# BotMod.net
KiCad netlist of a schematic drawn in EAGLE
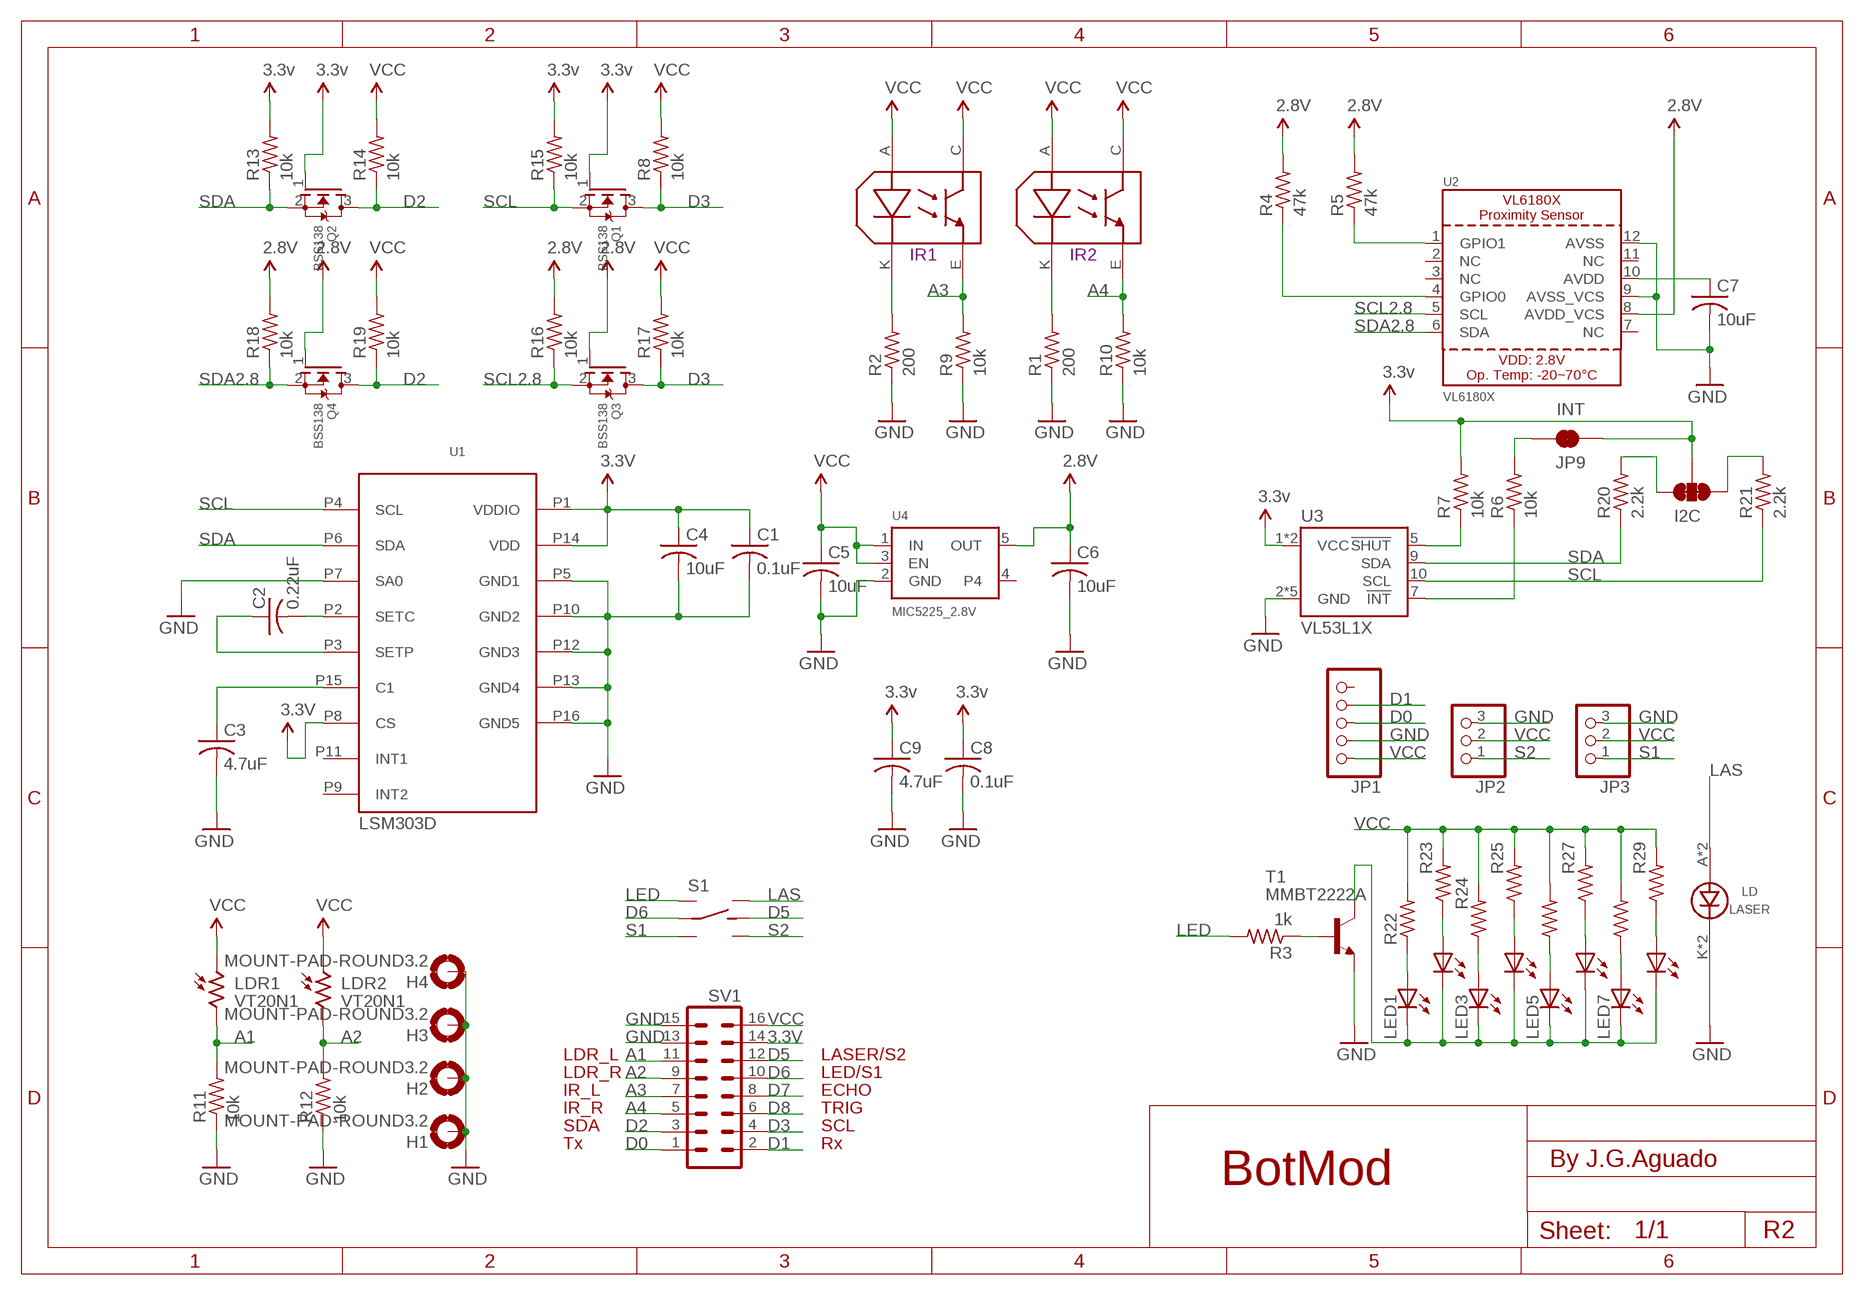
[diagram p0: schematic, sheet 1]

(export (version "E")
  (design (tool "Eeschema 10.0.6"))
  (components
    (comp (ref "C1")
      (value "0.1uF")
      (footprint "eagle-import:0402")
      (libsource (lib "eagle-import") (part "C0402"))
    )
    (comp (ref "C2")
      (value "0.22uF")
      (footprint "eagle-import:0402")
      (libsource (lib "eagle-import") (part "C0402"))
    )
    (comp (ref "C3")
      (value "4.7uF")
      (footprint "eagle-import:0402")
      (libsource (lib "eagle-import") (part "C0402"))
    )
    (comp (ref "C4")
      (value "10uF")
      (footprint "eagle-import:0402")
      (libsource (lib "eagle-import") (part "C0402"))
    )
    (comp (ref "C5")
      (value "10uF")
      (footprint "eagle-import:0402")
      (libsource (lib "eagle-import") (part "C0402"))
    )
    (comp (ref "C6")
      (value "10uF")
      (footprint "eagle-import:0402")
      (libsource (lib "eagle-import") (part "C0402"))
    )
    (comp (ref "C7")
      (value "10uF")
      (footprint "eagle-import:0402")
      (libsource (lib "eagle-import") (part "C0402"))
    )
    (comp (ref "C8")
      (value "0.1uF")
      (footprint "eagle-import:0402")
      (libsource (lib "eagle-import") (part "C0402"))
    )
    (comp (ref "C9")
      (value "4.7uF")
      (footprint "eagle-import:0402")
      (libsource (lib "eagle-import") (part "C0402"))
    )
    (comp (ref "H1")
      (value "MOUNT-PAD-ROUND3.2")
      (footprint "eagle-import:3,2-PAD")
      (libsource (lib "eagle-import") (part "MOUNT-PAD-ROUND3.2"))
    )
    (comp (ref "H2")
      (value "MOUNT-PAD-ROUND3.2")
      (footprint "eagle-import:3,2-PAD")
      (libsource (lib "eagle-import") (part "MOUNT-PAD-ROUND3.2"))
    )
    (comp (ref "H3")
      (value "MOUNT-PAD-ROUND3.2")
      (footprint "eagle-import:3,2-PAD")
      (libsource (lib "eagle-import") (part "MOUNT-PAD-ROUND3.2"))
    )
    (comp (ref "H4")
      (value "MOUNT-PAD-ROUND3.2")
      (footprint "eagle-import:3,2-PAD")
      (libsource (lib "eagle-import") (part "MOUNT-PAD-ROUND3.2"))
    )
    (comp (ref "I2C")
      (value "JUMPER-SMT_3_2-NC_TRACE_SILK")
      (footprint "eagle-import:SMT-JUMPER_3_2-NC_TRACE_SILK")
      (libsource (lib "eagle-import") (part "JUMPER-SMT_3_2-NC_TRACE_SILK"))
    )
    (comp (ref "IR1")
      (value "IR_TCRT5000")
      (footprint "eagle-import:IR_TCRT5000")
      (libsource (lib "eagle-import") (part "IR_TCRT5000"))
    )
    (comp (ref "IR2")
      (value "IR_TCRT5000")
      (footprint "eagle-import:IR_TCRT5000")
      (libsource (lib "eagle-import") (part "IR_TCRT5000"))
    )
    (comp (ref "JP1")
      (value "PINHEAD_5_FEMALE")
      (footprint "eagle-import:PINHEAD_5_FEMALE")
      (libsource (lib "eagle-import") (part "PINHEAD_5_FEMALE"))
    )
    (comp (ref "JP2")
      (value "PINHD-1X3")
      (footprint "eagle-import:1X03")
      (libsource (lib "eagle-import") (part "PINHD-1X3"))
    )
    (comp (ref "JP3")
      (value "PINHD-1X3")
      (footprint "eagle-import:1X03")
      (libsource (lib "eagle-import") (part "PINHD-1X3"))
    )
    (comp (ref "JP9")
      (value "INT")
      (footprint "eagle-import:PAD-JUMPER-2-NC_BY_TRACE_YES_SILK")
      (libsource (lib "eagle-import") (part "JUMPER-PAD-2-NC_BY_TRACE"))
    )
    (comp (ref "LD")
      (value "LASER")
      (footprint "eagle-import:KEYES_LASER")
      (libsource (lib "eagle-import") (part "KEYES_LASER"))
    )
    (comp (ref "LDR1")
      (value "VT20N1")
      (footprint "eagle-import:TO46-VT200")
      (libsource (lib "eagle-import") (part "VT20N1"))
    )
    (comp (ref "LDR2")
      (value "VT20N1")
      (footprint "eagle-import:TO46-VT200")
      (libsource (lib "eagle-import") (part "VT20N1"))
    )
    (comp (ref "LED1")
      (value "LED5730")
      (footprint "eagle-import:LED5730")
      (libsource (lib "eagle-import") (part "LED5730"))
    )
    (comp (ref "LED2")
      (value "LED5730")
      (footprint "eagle-import:LED5730")
      (libsource (lib "eagle-import") (part "LED5730"))
    )
    (comp (ref "LED3")
      (value "LED5730")
      (footprint "eagle-import:LED5730")
      (libsource (lib "eagle-import") (part "LED5730"))
    )
    (comp (ref "LED4")
      (value "LED5730")
      (footprint "eagle-import:LED5730")
      (libsource (lib "eagle-import") (part "LED5730"))
    )
    (comp (ref "LED5")
      (value "LED5730")
      (footprint "eagle-import:LED5730")
      (libsource (lib "eagle-import") (part "LED5730"))
    )
    (comp (ref "LED6")
      (value "LED5730")
      (footprint "eagle-import:LED5730")
      (libsource (lib "eagle-import") (part "LED5730"))
    )
    (comp (ref "LED7")
      (value "LED5730")
      (footprint "eagle-import:LED5730")
      (libsource (lib "eagle-import") (part "LED5730"))
    )
    (comp (ref "LED8")
      (value "LED5730")
      (footprint "eagle-import:LED5730")
      (libsource (lib "eagle-import") (part "LED5730"))
    )
    (comp (ref "Q1")
      (value "BSS138")
      (footprint "eagle-import:SOT23")
      (libsource (lib "eagle-import") (part "MOSFET-NREFLOW"))
    )
    (comp (ref "Q2")
      (value "BSS138")
      (footprint "eagle-import:SOT23")
      (libsource (lib "eagle-import") (part "MOSFET-NREFLOW"))
    )
    (comp (ref "Q3")
      (value "BSS138")
      (footprint "eagle-import:SOT23")
      (libsource (lib "eagle-import") (part "MOSFET-NREFLOW"))
    )
    (comp (ref "Q4")
      (value "BSS138")
      (footprint "eagle-import:SOT23")
      (libsource (lib "eagle-import") (part "MOSFET-NREFLOW"))
    )
    (comp (ref "R1")
      (value "200")
      (footprint "eagle-import:0402")
      (libsource (lib "eagle-import") (part "R0402"))
    )
    (comp (ref "R2")
      (value "200")
      (footprint "eagle-import:0402")
      (libsource (lib "eagle-import") (part "R0402"))
    )
    (comp (ref "R3")
      (value "1k")
      (footprint "eagle-import:0402")
      (libsource (lib "eagle-import") (part "R0402"))
    )
    (comp (ref "R4")
      (value "47k")
      (footprint "eagle-import:0402")
      (libsource (lib "eagle-import") (part "R0402"))
    )
    (comp (ref "R5")
      (value "47k")
      (footprint "eagle-import:0402")
      (libsource (lib "eagle-import") (part "R0402"))
    )
    (comp (ref "R6")
      (value "10k")
      (footprint "eagle-import:0402")
      (libsource (lib "eagle-import") (part "R0402"))
    )
    (comp (ref "R7")
      (value "10k")
      (footprint "eagle-import:0402")
      (libsource (lib "eagle-import") (part "R0402"))
    )
    (comp (ref "R8")
      (value "10k")
      (footprint "eagle-import:0402")
      (libsource (lib "eagle-import") (part "R0402"))
    )
    (comp (ref "R9")
      (value "10k")
      (footprint "eagle-import:0402")
      (libsource (lib "eagle-import") (part "R0402"))
    )
    (comp (ref "R10")
      (value "10k")
      (footprint "eagle-import:0402")
      (libsource (lib "eagle-import") (part "R0402"))
    )
    (comp (ref "R11")
      (value "10k")
      (footprint "eagle-import:0402")
      (libsource (lib "eagle-import") (part "R0402"))
    )
    (comp (ref "R12")
      (value "10k")
      (footprint "eagle-import:0402")
      (libsource (lib "eagle-import") (part "R0402"))
    )
    (comp (ref "R13")
      (value "10k")
      (footprint "eagle-import:0402")
      (libsource (lib "eagle-import") (part "R0402"))
    )
    (comp (ref "R14")
      (value "10k")
      (footprint "eagle-import:0402")
      (libsource (lib "eagle-import") (part "R0402"))
    )
    (comp (ref "R15")
      (value "10k")
      (footprint "eagle-import:0402")
      (libsource (lib "eagle-import") (part "R0402"))
    )
    (comp (ref "R16")
      (value "10k")
      (footprint "eagle-import:0402")
      (libsource (lib "eagle-import") (part "R0402"))
    )
    (comp (ref "R17")
      (value "10k")
      (footprint "eagle-import:0402")
      (libsource (lib "eagle-import") (part "R0402"))
    )
    (comp (ref "R18")
      (value "10k")
      (footprint "eagle-import:0402")
      (libsource (lib "eagle-import") (part "R0402"))
    )
    (comp (ref "R19")
      (value "10k")
      (footprint "eagle-import:0402")
      (libsource (lib "eagle-import") (part "R0402"))
    )
    (comp (ref "R20")
      (value "2.2k")
      (footprint "eagle-import:0402")
      (libsource (lib "eagle-import") (part "R0402"))
    )
    (comp (ref "R21")
      (value "2.2k")
      (footprint "eagle-import:0402")
      (libsource (lib "eagle-import") (part "R0402"))
    )
    (comp (ref "R22")
      (value "R1206")
      (footprint "eagle-import:1206")
      (libsource (lib "eagle-import") (part "R1206"))
    )
    (comp (ref "R23")
      (value "R1206")
      (footprint "eagle-import:1206")
      (libsource (lib "eagle-import") (part "R1206"))
    )
    (comp (ref "R24")
      (value "R1206")
      (footprint "eagle-import:1206")
      (libsource (lib "eagle-import") (part "R1206"))
    )
    (comp (ref "R25")
      (value "R1206")
      (footprint "eagle-import:1206")
      (libsource (lib "eagle-import") (part "R1206"))
    )
    (comp (ref "R26")
      (value "R1206")
      (footprint "eagle-import:1206")
      (libsource (lib "eagle-import") (part "R1206"))
    )
    (comp (ref "R27")
      (value "R1206")
      (footprint "eagle-import:1206")
      (libsource (lib "eagle-import") (part "R1206"))
    )
    (comp (ref "R28")
      (value "R1206")
      (footprint "eagle-import:1206")
      (libsource (lib "eagle-import") (part "R1206"))
    )
    (comp (ref "R29")
      (value "R1206")
      (footprint "eagle-import:1206")
      (libsource (lib "eagle-import") (part "R1206"))
    )
    (comp (ref "S1")
      (value "DPDT_JS202011CQN")
      (footprint "eagle-import:DPDT_JS202011CQN")
      (libsource (lib "eagle-import") (part "DPDT_JS202011CQN"))
    )
    (comp (ref "SV1")
      (value "MA08-2")
      (footprint "eagle-import:MA08-2")
      (libsource (lib "eagle-import") (part "MA08-2"))
    )
    (comp (ref "T1")
      (value "MMBT2222A")
      (footprint "eagle-import:SOT23-BEC")
      (libsource (lib "eagle-import") (part "-NPN-SOT23-BECBC808"))
    )
    (comp (ref "U1")
      (value "LSM303D")
      (footprint "eagle-import:LGA3X3_16L")
      (libsource (lib "eagle-import") (part "LSM303D"))
    )
    (comp (ref "U2")
      (value "VL6180X")
      (footprint "eagle-import:VL6180")
      (libsource (lib "eagle-import") (part "VL6180X"))
    )
    (comp (ref "U3")
      (value "VL53L1X")
      (footprint "eagle-import:VL53L1X")
      (libsource (lib "eagle-import") (part "VL53L1XSMD"))
    )
    (comp (ref "U4")
      (value "MIC5225_2.8V")
      (footprint "eagle-import:SOT23-5")
      (libsource (lib "eagle-import") (part "VREG_SOT23-5"))
    )
  )
  (nets
    (net (code "1") (name "/A1") (class "Default")
      (node (ref "LDR1") (pin "2") (pinfunction "2_2") (pintype "passive"))
      (node (ref "R11") (pin "2") (pinfunction "2_2") (pintype "passive"))
      (node (ref "SV1") (pin "11") (pinfunction "11_11") (pintype "passive"))
    )
    (net (code "2") (name "/A2") (class "Default")
      (node (ref "LDR2") (pin "2") (pinfunction "2_2") (pintype "passive"))
      (node (ref "R12") (pin "2") (pinfunction "2_2") (pintype "passive"))
      (node (ref "SV1") (pin "9") (pinfunction "9_9") (pintype "passive"))
    )
    (net (code "3") (name "/A3") (class "Default")
      (node (ref "IR1") (pin "E") (pinfunction "E_E") (pintype "bidirectional"))
      (node (ref "R9") (pin "2") (pinfunction "2_2") (pintype "passive"))
      (node (ref "SV1") (pin "7") (pinfunction "7_7") (pintype "passive"))
    )
    (net (code "4") (name "/A4") (class "Default")
      (node (ref "IR2") (pin "E") (pinfunction "E_E") (pintype "bidirectional"))
      (node (ref "R10") (pin "2") (pinfunction "2_2") (pintype "passive"))
      (node (ref "SV1") (pin "5") (pinfunction "5_5") (pintype "passive"))
    )
    (net (code "5") (name "/D0") (class "Default")
      (node (ref "JP1") (pin "P$3") (pinfunction "3_P$3") (pintype "passive"))
      (node (ref "SV1") (pin "1") (pinfunction "1_1") (pintype "passive"))
    )
    (net (code "6") (name "/D1") (class "Default")
      (node (ref "JP1") (pin "P$4") (pinfunction "4_P$4") (pintype "passive"))
      (node (ref "SV1") (pin "2") (pinfunction "2_2") (pintype "passive"))
    )
    (net (code "7") (name "/D2") (class "Default")
      (node (ref "Q2") (pin "3") (pinfunction "D_3") (pintype "bidirectional"))
      (node (ref "Q4") (pin "3") (pinfunction "D_3") (pintype "bidirectional"))
      (node (ref "R14") (pin "1") (pinfunction "1_1") (pintype "passive"))
      (node (ref "R19") (pin "1") (pinfunction "1_1") (pintype "passive"))
      (node (ref "SV1") (pin "3") (pinfunction "3_3") (pintype "passive"))
    )
    (net (code "8") (name "/D3") (class "Default")
      (node (ref "Q1") (pin "3") (pinfunction "D_3") (pintype "bidirectional"))
      (node (ref "Q3") (pin "3") (pinfunction "D_3") (pintype "bidirectional"))
      (node (ref "R17") (pin "1") (pinfunction "1_1") (pintype "passive"))
      (node (ref "R8") (pin "1") (pinfunction "1_1") (pintype "passive"))
      (node (ref "SV1") (pin "4") (pinfunction "4_4") (pintype "passive"))
    )
    (net (code "9") (name "/D5") (class "Default")
      (node (ref "S1") (pin "5") (pinfunction "RC_5") (pintype "passive"))
      (node (ref "SV1") (pin "12") (pinfunction "12_12") (pintype "passive"))
    )
    (net (code "10") (name "/D6") (class "Default")
      (node (ref "S1") (pin "2") (pinfunction "LC_2") (pintype "passive"))
      (node (ref "SV1") (pin "10") (pinfunction "10_10") (pintype "passive"))
    )
    (net (code "11") (name "/D7") (class "Default")
      (node (ref "SV1") (pin "8") (pinfunction "8_8") (pintype "passive"))
    )
    (net (code "12") (name "/D8") (class "Default")
      (node (ref "SV1") (pin "6") (pinfunction "6_6") (pintype "passive"))
    )
    (net (code "13") (name "/LAS") (class "Default")
      (node (ref "LD") (pin "A") (pinfunction "A_A") (pintype "bidirectional"))
      (node (ref "LD") (pin "A1") (pinfunction "A_A1") (pintype "bidirectional"))
      (node (ref "S1") (pin "4") (pinfunction "R1_4") (pintype "passive"))
    )
    (net (code "14") (name "/LED") (class "Default")
      (node (ref "R3") (pin "2") (pinfunction "2_2") (pintype "passive"))
      (node (ref "S1") (pin "1") (pinfunction "L1_1") (pintype "passive"))
    )
    (net (code "15") (name "/S1") (class "Default")
      (node (ref "JP3") (pin "1") (pinfunction "1_1") (pintype "passive"))
      (node (ref "S1") (pin "3") (pinfunction "L2_3") (pintype "passive"))
    )
    (net (code "16") (name "/S2") (class "Default")
      (node (ref "JP2") (pin "1") (pinfunction "1_1") (pintype "passive"))
      (node (ref "S1") (pin "6") (pinfunction "R2_6") (pintype "passive"))
    )
    (net (code "17") (name "/SCL") (class "Default")
      (node (ref "Q1") (pin "2") (pinfunction "S_2") (pintype "bidirectional"))
      (node (ref "R15") (pin "1") (pinfunction "1_1") (pintype "passive"))
      (node (ref "R21") (pin "1") (pinfunction "1_1") (pintype "passive"))
      (node (ref "U1") (pin "P4") (pinfunction "SCL_P4") (pintype "bidirectional"))
      (node (ref "U3") (pin "10") (pinfunction "SCL_10") (pintype "bidirectional"))
    )
    (net (code "18") (name "/SCL2.8") (class "Default")
      (node (ref "Q3") (pin "2") (pinfunction "S_2") (pintype "bidirectional"))
      (node (ref "R16") (pin "1") (pinfunction "1_1") (pintype "passive"))
      (node (ref "U2") (pin "5") (pinfunction "SCL_5") (pintype "input"))
    )
    (net (code "19") (name "/SDA") (class "Default")
      (node (ref "Q2") (pin "2") (pinfunction "S_2") (pintype "bidirectional"))
      (node (ref "R13") (pin "1") (pinfunction "1_1") (pintype "passive"))
      (node (ref "R20") (pin "1") (pinfunction "1_1") (pintype "passive"))
      (node (ref "U1") (pin "P6") (pinfunction "SDA_P6") (pintype "bidirectional"))
      (node (ref "U3") (pin "9") (pinfunction "SDA_9") (pintype "bidirectional"))
    )
    (net (code "20") (name "/SDA2.8") (class "Default")
      (node (ref "Q4") (pin "2") (pinfunction "S_2") (pintype "bidirectional"))
      (node (ref "R18") (pin "1") (pinfunction "1_1") (pintype "passive"))
      (node (ref "U2") (pin "6") (pinfunction "SDA_6") (pintype "bidirectional"))
    )
    (net (code "21") (name "2.8V") (class "Default")
      (node (ref "C6") (pin "1") (pinfunction "1_1") (pintype "passive"))
      (node (ref "Q3") (pin "1") (pinfunction "G_1") (pintype "bidirectional"))
      (node (ref "Q4") (pin "1") (pinfunction "G_1") (pintype "bidirectional"))
      (node (ref "R16") (pin "2") (pinfunction "2_2") (pintype "passive"))
      (node (ref "R18") (pin "2") (pinfunction "2_2") (pintype "passive"))
      (node (ref "R4") (pin "2") (pinfunction "2_2") (pintype "passive"))
      (node (ref "R5") (pin "2") (pinfunction "2_2") (pintype "passive"))
      (node (ref "U2") (pin "8") (pinfunction "AVDD_VCS_8") (pintype "power_in"))
      (node (ref "U4") (pin "5") (pinfunction "OUT_5") (pintype "power_in"))
    )
    (net (code "22") (name "3.3V") (class "Default")
      (node (ref "C1") (pin "1") (pinfunction "1_1") (pintype "passive"))
      (node (ref "C4") (pin "1") (pinfunction "1_1") (pintype "passive"))
      (node (ref "C8") (pin "1") (pinfunction "1_1") (pintype "passive"))
      (node (ref "C9") (pin "1") (pinfunction "1_1") (pintype "passive"))
      (node (ref "I2C") (pin "2") (pinfunction "2_2") (pintype "passive"))
      (node (ref "JP9") (pin "1") (pinfunction "1_1") (pintype "passive"))
      (node (ref "Q1") (pin "1") (pinfunction "G_1") (pintype "bidirectional"))
      (node (ref "Q2") (pin "1") (pinfunction "G_1") (pintype "bidirectional"))
      (node (ref "R13") (pin "2") (pinfunction "2_2") (pintype "passive"))
      (node (ref "R15") (pin "2") (pinfunction "2_2") (pintype "passive"))
      (node (ref "R7") (pin "2") (pinfunction "2_2") (pintype "passive"))
      (node (ref "SV1") (pin "14") (pinfunction "14_14") (pintype "passive"))
      (node (ref "U1") (pin "P1") (pinfunction "VDDIO_P1") (pintype "bidirectional"))
      (node (ref "U1") (pin "P14") (pinfunction "VDD_P14") (pintype "bidirectional"))
      (node (ref "U1") (pin "P8") (pinfunction "CS_P8") (pintype "bidirectional"))
      (node (ref "U3") (pin "1") (pinfunction "VCC_1") (pintype "bidirectional"))
      (node (ref "U3") (pin "11") (pinfunction "VCC_11") (pintype "bidirectional"))
    )
    (net (code "23") (name "GND") (class "Default")
      (node (ref "C1") (pin "2") (pinfunction "2_2") (pintype "passive"))
      (node (ref "C3") (pin "2") (pinfunction "2_2") (pintype "passive"))
      (node (ref "C4") (pin "2") (pinfunction "2_2") (pintype "passive"))
      (node (ref "C5") (pin "2") (pinfunction "2_2") (pintype "passive"))
      (node (ref "C6") (pin "2") (pinfunction "2_2") (pintype "passive"))
      (node (ref "C7") (pin "2") (pinfunction "2_2") (pintype "passive"))
      (node (ref "C8") (pin "2") (pinfunction "2_2") (pintype "passive"))
      (node (ref "C9") (pin "2") (pinfunction "2_2") (pintype "passive"))
      (node (ref "H1") (pin "B3,2") (pinfunction "MOUNT_B3,2") (pintype "passive"))
      (node (ref "H2") (pin "B3,2") (pinfunction "MOUNT_B3,2") (pintype "passive"))
      (node (ref "H3") (pin "B3,2") (pinfunction "MOUNT_B3,2") (pintype "passive"))
      (node (ref "H4") (pin "B3,2") (pinfunction "MOUNT_B3,2") (pintype "passive"))
      (node (ref "JP1") (pin "P$2") (pinfunction "2_P$2") (pintype "passive"))
      (node (ref "JP2") (pin "3") (pinfunction "3_3") (pintype "passive"))
      (node (ref "JP3") (pin "3") (pinfunction "3_3") (pintype "passive"))
      (node (ref "LD") (pin "K") (pinfunction "K_K") (pintype "bidirectional"))
      (node (ref "LD") (pin "K1") (pinfunction "K_K1") (pintype "bidirectional"))
      (node (ref "R1") (pin "1") (pinfunction "1_1") (pintype "passive"))
      (node (ref "R10") (pin "1") (pinfunction "1_1") (pintype "passive"))
      (node (ref "R11") (pin "1") (pinfunction "1_1") (pintype "passive"))
      (node (ref "R12") (pin "1") (pinfunction "1_1") (pintype "passive"))
      (node (ref "R2") (pin "1") (pinfunction "1_1") (pintype "passive"))
      (node (ref "R9") (pin "1") (pinfunction "1_1") (pintype "passive"))
      (node (ref "SV1") (pin "13") (pinfunction "13_13") (pintype "passive"))
      (node (ref "SV1") (pin "15") (pinfunction "15_15") (pintype "passive"))
      (node (ref "T1") (pin "E") (pinfunction "E_E") (pintype "passive"))
      (node (ref "U1") (pin "P10") (pinfunction "GND2_P10") (pintype "bidirectional"))
      (node (ref "U1") (pin "P12") (pinfunction "GND3_P12") (pintype "bidirectional"))
      (node (ref "U1") (pin "P13") (pinfunction "GND4_P13") (pintype "bidirectional"))
      (node (ref "U1") (pin "P16") (pinfunction "GND5_P16") (pintype "bidirectional"))
      (node (ref "U1") (pin "P5") (pinfunction "GND1_P5") (pintype "bidirectional"))
      (node (ref "U1") (pin "P7") (pinfunction "SA0_P7") (pintype "bidirectional"))
      (node (ref "U2") (pin "12") (pinfunction "AVSS_12") (pintype "power_in"))
      (node (ref "U2") (pin "9") (pinfunction "AVSS_VCS_9") (pintype "power_in"))
      (node (ref "U3") (pin "12") (pinfunction "GND_12") (pintype "bidirectional"))
      (node (ref "U3") (pin "2") (pinfunction "GND_2") (pintype "bidirectional"))
      (node (ref "U3") (pin "3") (pinfunction "GND_3") (pintype "bidirectional"))
      (node (ref "U3") (pin "4") (pinfunction "GND_4") (pintype "bidirectional"))
      (node (ref "U3") (pin "6") (pinfunction "GND_6") (pintype "bidirectional"))
      (node (ref "U4") (pin "2") (pinfunction "GND_2") (pintype "power_in"))
    )
    (net (code "24") (name "Net-(I2C-Pad1)") (class "Default")
      (node (ref "I2C") (pin "1") (pinfunction "1_1") (pintype "passive"))
      (node (ref "R21") (pin "2") (pinfunction "2_2") (pintype "passive"))
    )
    (net (code "25") (name "Net-(I2C-Pad3)") (class "Default")
      (node (ref "I2C") (pin "3") (pinfunction "3_3") (pintype "passive"))
      (node (ref "R20") (pin "2") (pinfunction "2_2") (pintype "passive"))
    )
    (net (code "26") (name "Net-(IR1-PadK)") (class "Default")
      (node (ref "IR1") (pin "K") (pinfunction "K_K") (pintype "bidirectional"))
      (node (ref "R2") (pin "2") (pinfunction "2_2") (pintype "passive"))
    )
    (net (code "27") (name "Net-(IR2-PadK)") (class "Default")
      (node (ref "IR2") (pin "K") (pinfunction "K_K") (pintype "bidirectional"))
      (node (ref "R1") (pin "2") (pinfunction "2_2") (pintype "passive"))
    )
    (net (code "28") (name "Net-(JP9-Pad2)") (class "Default")
      (node (ref "JP9") (pin "2") (pinfunction "2_2") (pintype "passive"))
      (node (ref "R6") (pin "2") (pinfunction "2_2") (pintype "passive"))
    )
    (net (code "29") (name "Net-(LED1-A)") (class "Default")
      (node (ref "LED1") (pin "P$1") (pinfunction "A_P$1") (pintype "passive"))
      (node (ref "R22") (pin "1") (pinfunction "1_1") (pintype "passive"))
    )
    (net (code "30") (name "Net-(LED1-C)") (class "Default")
      (node (ref "LED1") (pin "P$2") (pinfunction "C_P$2") (pintype "passive"))
      (node (ref "LED2") (pin "P$2") (pinfunction "C_P$2") (pintype "passive"))
      (node (ref "LED3") (pin "P$2") (pinfunction "C_P$2") (pintype "passive"))
      (node (ref "LED4") (pin "P$2") (pinfunction "C_P$2") (pintype "passive"))
      (node (ref "LED5") (pin "P$2") (pinfunction "C_P$2") (pintype "passive"))
      (node (ref "LED6") (pin "P$2") (pinfunction "C_P$2") (pintype "passive"))
      (node (ref "LED7") (pin "P$2") (pinfunction "C_P$2") (pintype "passive"))
      (node (ref "LED8") (pin "P$2") (pinfunction "C_P$2") (pintype "passive"))
      (node (ref "T1") (pin "C") (pinfunction "C_C") (pintype "passive"))
    )
    (net (code "31") (name "Net-(LED2-A)") (class "Default")
      (node (ref "LED2") (pin "P$1") (pinfunction "A_P$1") (pintype "passive"))
      (node (ref "R23") (pin "1") (pinfunction "1_1") (pintype "passive"))
    )
    (net (code "32") (name "Net-(LED3-A)") (class "Default")
      (node (ref "LED3") (pin "P$1") (pinfunction "A_P$1") (pintype "passive"))
      (node (ref "R24") (pin "1") (pinfunction "1_1") (pintype "passive"))
    )
    (net (code "33") (name "Net-(LED4-A)") (class "Default")
      (node (ref "LED4") (pin "P$1") (pinfunction "A_P$1") (pintype "passive"))
      (node (ref "R25") (pin "1") (pinfunction "1_1") (pintype "passive"))
    )
    (net (code "34") (name "Net-(LED5-A)") (class "Default")
      (node (ref "LED5") (pin "P$1") (pinfunction "A_P$1") (pintype "passive"))
      (node (ref "R26") (pin "1") (pinfunction "1_1") (pintype "passive"))
    )
    (net (code "35") (name "Net-(LED6-A)") (class "Default")
      (node (ref "LED6") (pin "P$1") (pinfunction "A_P$1") (pintype "passive"))
      (node (ref "R27") (pin "1") (pinfunction "1_1") (pintype "passive"))
    )
    (net (code "36") (name "Net-(LED7-A)") (class "Default")
      (node (ref "LED7") (pin "P$1") (pinfunction "A_P$1") (pintype "passive"))
      (node (ref "R28") (pin "1") (pinfunction "1_1") (pintype "passive"))
    )
    (net (code "37") (name "Net-(LED8-A)") (class "Default")
      (node (ref "LED8") (pin "P$1") (pinfunction "A_P$1") (pintype "passive"))
      (node (ref "R29") (pin "1") (pinfunction "1_1") (pintype "passive"))
    )
    (net (code "38") (name "Net-(R3-Pad1)") (class "Default")
      (node (ref "R3") (pin "1") (pinfunction "1_1") (pintype "passive"))
      (node (ref "T1") (pin "B") (pinfunction "B_B") (pintype "passive"))
    )
    (net (code "39") (name "Net-(U1-C1)") (class "Default")
      (node (ref "C3") (pin "1") (pinfunction "1_1") (pintype "passive"))
      (node (ref "U1") (pin "P15") (pinfunction "C1_P15") (pintype "bidirectional"))
    )
    (net (code "40") (name "Net-(U1-SETC)") (class "Default")
      (node (ref "C2") (pin "2") (pinfunction "2_2") (pintype "passive"))
      (node (ref "U1") (pin "P2") (pinfunction "SETC_P2") (pintype "bidirectional"))
    )
    (net (code "41") (name "Net-(U1-SETP)") (class "Default")
      (node (ref "C2") (pin "1") (pinfunction "1_1") (pintype "passive"))
      (node (ref "U1") (pin "P3") (pinfunction "SETP_P3") (pintype "bidirectional"))
    )
    (net (code "42") (name "Net-(U2-AVDD)") (class "Default")
      (node (ref "C7") (pin "1") (pinfunction "1_1") (pintype "passive"))
      (node (ref "U2") (pin "10") (pinfunction "AVDD_10") (pintype "power_in"))
    )
    (net (code "43") (name "Net-(U2-GPIO0)") (class "Default")
      (node (ref "R4") (pin "1") (pinfunction "1_1") (pintype "passive"))
      (node (ref "U2") (pin "4") (pinfunction "GPIO0_4") (pintype "bidirectional"))
    )
    (net (code "44") (name "Net-(U2-GPIO1)") (class "Default")
      (node (ref "R5") (pin "1") (pinfunction "1_1") (pintype "passive"))
      (node (ref "U2") (pin "1") (pinfunction "GPIO1_1") (pintype "bidirectional"))
    )
    (net (code "45") (name "Net-(U3-~{INT})") (class "Default")
      (node (ref "R6") (pin "1") (pinfunction "1_1") (pintype "passive"))
      (node (ref "U3") (pin "7") (pinfunction "~{INT}_7") (pintype "bidirectional"))
    )
    (net (code "46") (name "Net-(U3-~{SHUT})") (class "Default")
      (node (ref "R7") (pin "1") (pinfunction "1_1") (pintype "passive"))
      (node (ref "U3") (pin "5") (pinfunction "~{SHUT}_5") (pintype "bidirectional"))
    )
    (net (code "47") (name "VCC") (class "Default")
      (node (ref "C5") (pin "1") (pinfunction "1_1") (pintype "passive"))
      (node (ref "IR1") (pin "A") (pinfunction "A_A") (pintype "bidirectional"))
      (node (ref "IR1") (pin "C") (pinfunction "C_C") (pintype "bidirectional"))
      (node (ref "IR2") (pin "A") (pinfunction "A_A") (pintype "bidirectional"))
      (node (ref "IR2") (pin "C") (pinfunction "C_C") (pintype "bidirectional"))
      (node (ref "JP1") (pin "P$1") (pinfunction "1_P$1") (pintype "passive"))
      (node (ref "JP2") (pin "2") (pinfunction "2_2") (pintype "passive"))
      (node (ref "JP3") (pin "2") (pinfunction "2_2") (pintype "passive"))
      (node (ref "LDR1") (pin "1") (pinfunction "1_1") (pintype "passive"))
      (node (ref "LDR2") (pin "1") (pinfunction "1_1") (pintype "passive"))
      (node (ref "R14") (pin "2") (pinfunction "2_2") (pintype "passive"))
      (node (ref "R17") (pin "2") (pinfunction "2_2") (pintype "passive"))
      (node (ref "R19") (pin "2") (pinfunction "2_2") (pintype "passive"))
      (node (ref "R22") (pin "2") (pinfunction "2_2") (pintype "passive"))
      (node (ref "R23") (pin "2") (pinfunction "2_2") (pintype "passive"))
      (node (ref "R24") (pin "2") (pinfunction "2_2") (pintype "passive"))
      (node (ref "R25") (pin "2") (pinfunction "2_2") (pintype "passive"))
      (node (ref "R26") (pin "2") (pinfunction "2_2") (pintype "passive"))
      (node (ref "R27") (pin "2") (pinfunction "2_2") (pintype "passive"))
      (node (ref "R28") (pin "2") (pinfunction "2_2") (pintype "passive"))
      (node (ref "R29") (pin "2") (pinfunction "2_2") (pintype "passive"))
      (node (ref "R8") (pin "2") (pinfunction "2_2") (pintype "passive"))
      (node (ref "SV1") (pin "16") (pinfunction "16_16") (pintype "passive"))
      (node (ref "U4") (pin "1") (pinfunction "IN_1") (pintype "power_in"))
      (node (ref "U4") (pin "3") (pinfunction "EN_3") (pintype "input"))
    )
    (net (code "48") (name "unconnected-(JP1-5-PadP$5)") (class "Default")
      (node (ref "JP1") (pin "P$5") (pinfunction "5_P$5") (pintype "passive"))
    )
    (net (code "49") (name "unconnected-(U1-INT1-PadP11)") (class "Default")
      (node (ref "U1") (pin "P11") (pinfunction "INT1_P11") (pintype "bidirectional"))
    )
    (net (code "50") (name "unconnected-(U1-INT2-PadP9)") (class "Default")
      (node (ref "U1") (pin "P9") (pinfunction "INT2_P9") (pintype "bidirectional"))
    )
    (net (code "51") (name "unconnected-(U2-NC-Pad2)") (class "Default")
      (node (ref "U2") (pin "2") (pinfunction "NC_2") (pintype "no_connect"))
    )
    (net (code "52") (name "unconnected-(U2-NC-Pad3)") (class "Default")
      (node (ref "U2") (pin "3") (pinfunction "NC_3") (pintype "no_connect"))
    )
    (net (code "53") (name "unconnected-(U2-NC-Pad7)") (class "Default")
      (node (ref "U2") (pin "7") (pinfunction "NC_7") (pintype "no_connect"))
    )
    (net (code "54") (name "unconnected-(U2-NC-Pad11)") (class "Default")
      (node (ref "U2") (pin "11") (pinfunction "NC_11") (pintype "no_connect"))
    )
    (net (code "55") (name "unconnected-(U4-P4-Pad4)") (class "Default")
      (node (ref "U4") (pin "4") (pinfunction "P4_4") (pintype "bidirectional"))
    )
  )
)
